# PiPowerHat.net
KiCad netlist of a schematic drawn in EAGLE
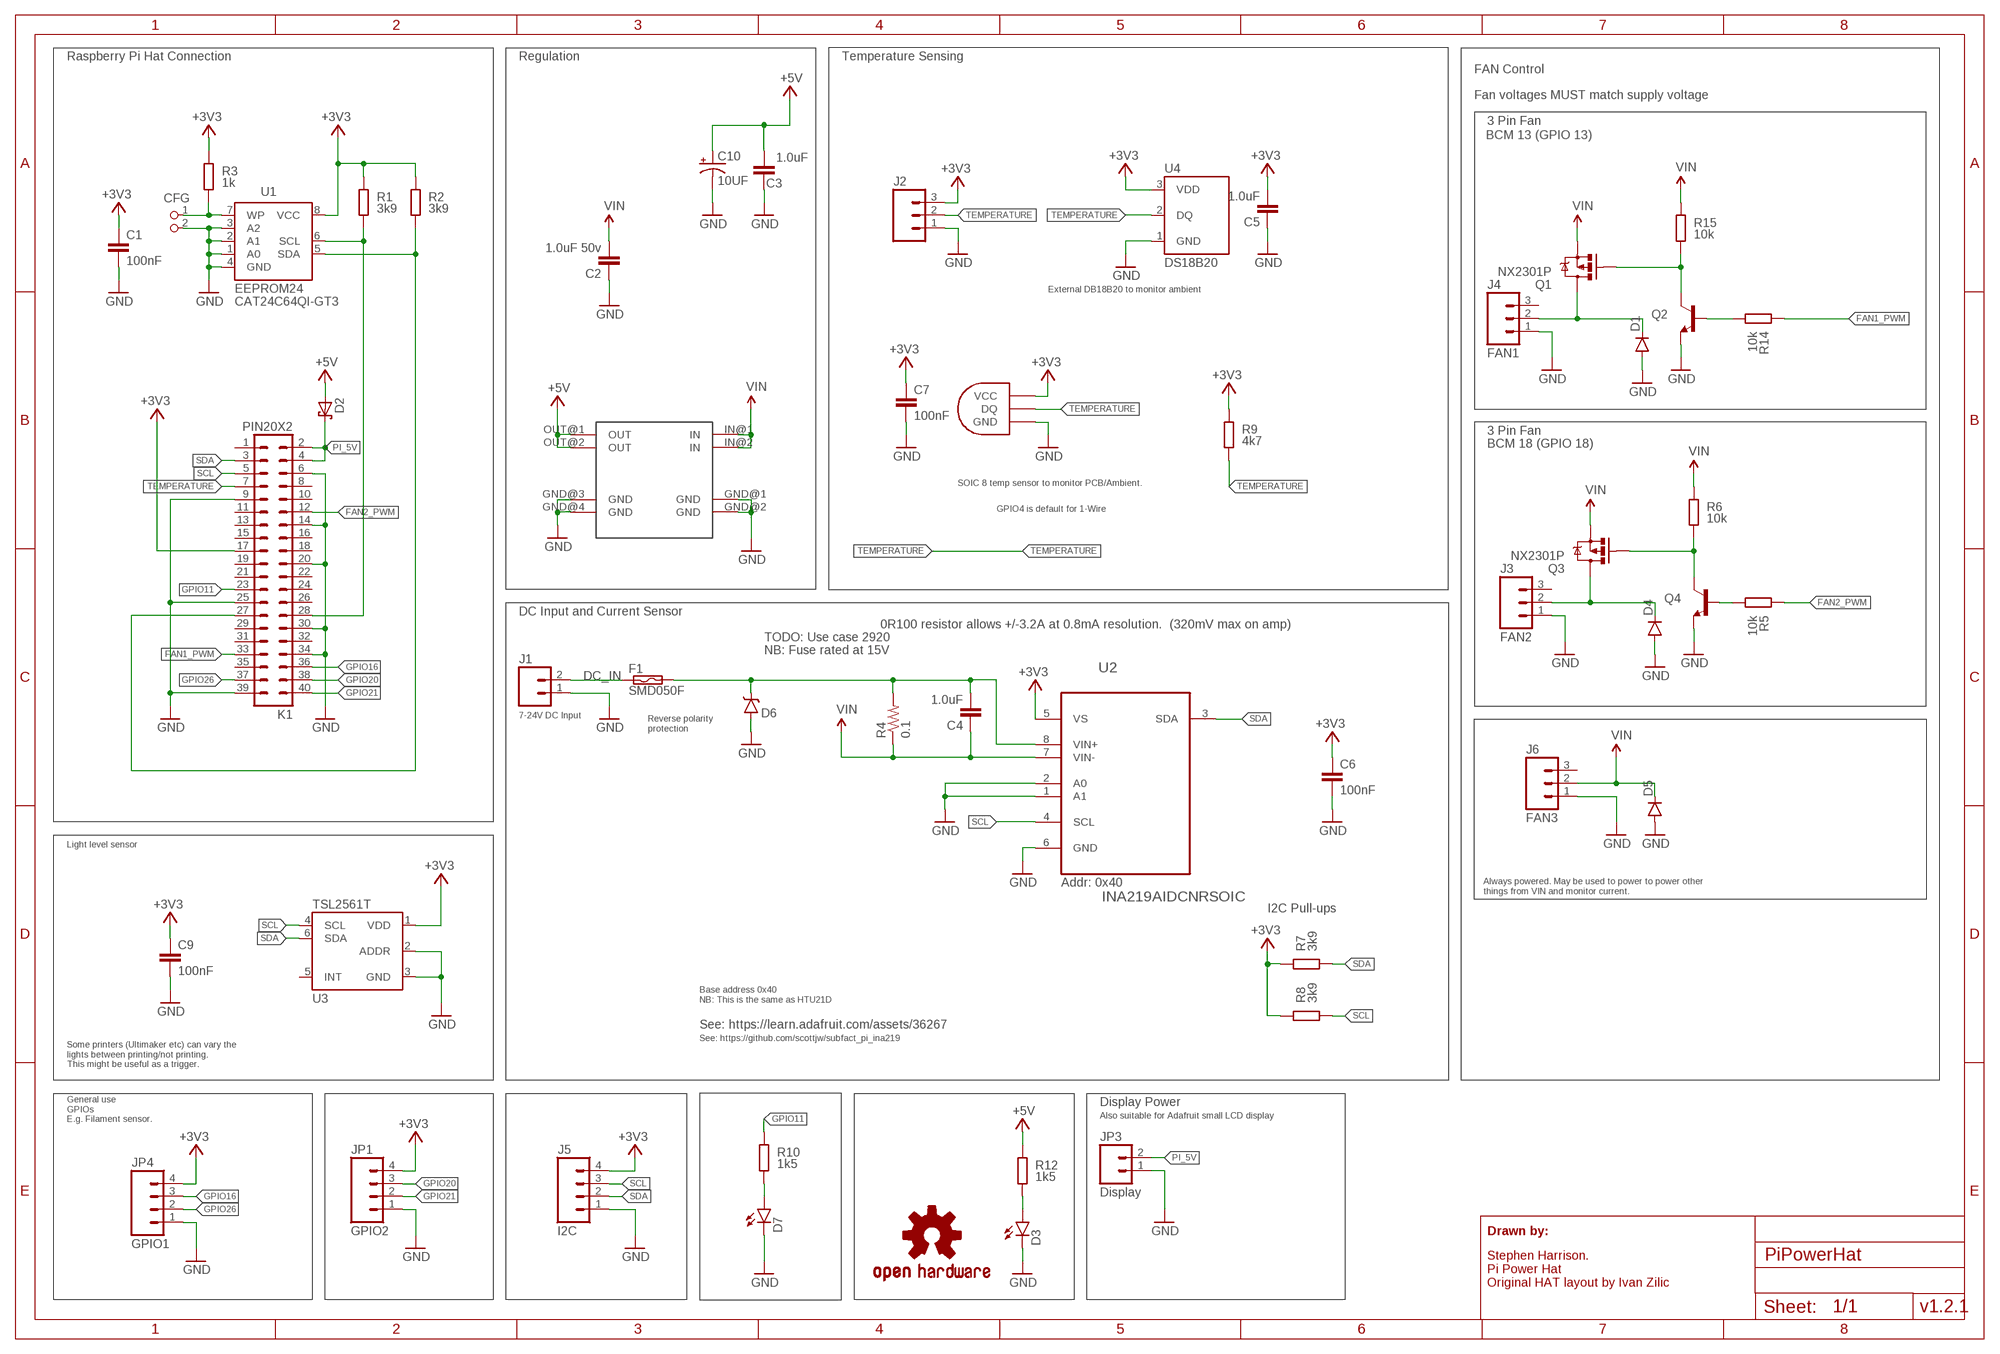
[diagram p0: schematic, sheet 1]

(export (version "E")
  (design (tool "Eeschema 10.0.6"))
  (components
    (comp (ref "C1")
      (value "100nF")
      (footprint "eagle-import:C0805K")
      (libsource (lib "eagle-import") (part "C-EUC0805K"))
    )
    (comp (ref "C2")
      (value "1.0uF 50v")
      (footprint "eagle-import:0805-CAP")
      (libsource (lib "eagle-import") (part "1.0UF-25V-+80/-20(0805){dblquote}"))
    )
    (comp (ref "C3")
      (value "1.0uF")
      (footprint "eagle-import:0805-CAP")
      (libsource (lib "eagle-import") (part "1.0UF-25V-+80/-20(0805){dblquote}"))
    )
    (comp (ref "C4")
      (value "1.0uF")
      (footprint "eagle-import:0805-CAP")
      (libsource (lib "eagle-import") (part "1.0UF-25V-+80/-20(0805){dblquote}"))
    )
    (comp (ref "C5")
      (value "1.0uF")
      (footprint "eagle-import:0805-CAP")
      (libsource (lib "eagle-import") (part "1.0UF-25V-+80/-20(0805){dblquote}"))
    )
    (comp (ref "C6")
      (value "100nF")
      (footprint "eagle-import:C0805K")
      (libsource (lib "eagle-import") (part "C-EUC0805K"))
    )
    (comp (ref "C7")
      (value "100nF")
      (footprint "eagle-import:C0805K")
      (libsource (lib "eagle-import") (part "C-EUC0805K"))
    )
    (comp (ref "C9")
      (value "100nF")
      (footprint "eagle-import:C0805K")
      (libsource (lib "eagle-import") (part "C-EUC0805K"))
    )
    (comp (ref "C10")
      (value "10UF")
      (footprint "eagle-import:EIA6032-NOM")
      (libsource (lib "eagle-import") (part "10UF-25V-10%(SMT-TANT)"))
    )
    (comp (ref "CFG")
      (value "PIN2_100")
      (footprint "eagle-import:PIN_W_2")
      (libsource (lib "eagle-import") (part "PIN2_100"))
    )
    (comp (ref "D1")
      (value "DIODESOD123")
      (footprint "eagle-import:SOD-123")
      (libsource (lib "eagle-import") (part "DIODESOD123"))
    )
    (comp (ref "D2")
      (value "MBRS340T3G")
      (footprint "eagle-import:SMC")
      (libsource (lib "eagle-import") (part "SCHOTTKY-DIODESMC"))
    )
    (comp (ref "D3")
      (value "LED1206-BOTTOM")
      (footprint "eagle-import:LED-1206-BOTTOM")
      (libsource (lib "eagle-import") (part "LED1206-BOTTOM"))
    )
    (comp (ref "D4")
      (value "DIODESOD123")
      (footprint "eagle-import:SOD-123")
      (libsource (lib "eagle-import") (part "DIODESOD123"))
    )
    (comp (ref "D5")
      (value "DIODESOD123")
      (footprint "eagle-import:SOD-123")
      (libsource (lib "eagle-import") (part "DIODESOD123"))
    )
    (comp (ref "D6")
      (value "B340A")
      (footprint "eagle-import:SMA-DIODE")
      (libsource (lib "eagle-import") (part "DIODE-SCHOTTKY-B340A"))
    )
    (comp (ref "D7")
      (value "LED1206")
      (footprint "eagle-import:LED-1206")
      (libsource (lib "eagle-import") (part "LED1206"))
    )
    (comp (ref "F1")
      (value "SMD050F")
      (footprint "eagle-import:SMD050F")
      (libsource (lib "eagle-import") (part "SMDF050"))
    )
    (comp (ref "J1")
      (value "M025MM")
      (footprint "eagle-import:SCREWTERMINAL-5MM-2")
      (libsource (lib "eagle-import") (part "M025MM"))
    )
    (comp (ref "J2")
      (value "M03POLAR")
      (footprint "eagle-import:MOLEX-1X3")
      (libsource (lib "eagle-import") (part "M03POLAR"))
    )
    (comp (ref "J3")
      (value "FAN2")
      (footprint "eagle-import:MOLEX-1X3")
      (libsource (lib "eagle-import") (part "M03POLAR"))
    )
    (comp (ref "J4")
      (value "FAN1")
      (footprint "eagle-import:MOLEX-1X3")
      (libsource (lib "eagle-import") (part "M03POLAR"))
    )
    (comp (ref "J5")
      (value "I2C")
      (footprint "eagle-import:MOLEX-1X4")
      (libsource (lib "eagle-import") (part "M04POLAR"))
    )
    (comp (ref "J6")
      (value "FAN3")
      (footprint "eagle-import:MOLEX-1X3")
      (libsource (lib "eagle-import") (part "M03POLAR"))
    )
    (comp (ref "JP1")
      (value "GPIO2")
      (footprint "eagle-import:MOLEX-1X4")
      (libsource (lib "eagle-import") (part "M04POLAR"))
    )
    (comp (ref "JP3")
      (value "Display")
      (footprint "eagle-import:MOLEX-1X2")
      (libsource (lib "eagle-import") (part "M02POLAR"))
    )
    (comp (ref "JP4")
      (value "GPIO1")
      (footprint "eagle-import:MOLEX-1X4")
      (libsource (lib "eagle-import") (part "M04POLAR"))
    )
    (comp (ref "K1")
      (value "PIN20X2")
      (footprint "eagle-import:PIN_20X2")
      (libsource (lib "eagle-import") (part "PIN20X2"))
    )
    (comp (ref "LOGO1")
      (value "OSHW-LOGOM")
      (footprint "eagle-import:OSHW-LOGO-M")
      (libsource (lib "eagle-import") (part "OSHW-LOGOM"))
    )
    (comp (ref "Q1")
      (value "NX2301P")
      (footprint "eagle-import:SOT23-3")
      (libsource (lib "eagle-import") (part "MOSFET-PCHANNEL"))
    )
    (comp (ref "Q2")
      (value "TRANSISTOR_NPNSOT23-3")
      (footprint "eagle-import:SOT23-3")
      (libsource (lib "eagle-import") (part "TRANSISTOR_NPNSOT23-3"))
    )
    (comp (ref "Q3")
      (value "NX2301P")
      (footprint "eagle-import:SOT23-3")
      (libsource (lib "eagle-import") (part "MOSFET-PCHANNEL"))
    )
    (comp (ref "Q4")
      (value "TRANSISTOR_NPNSOT23-3")
      (footprint "eagle-import:SOT23-3")
      (libsource (lib "eagle-import") (part "TRANSISTOR_NPNSOT23-3"))
    )
    (comp (ref "R1")
      (value "3k9")
      (footprint "eagle-import:M0805")
      (fields (field (name "TOLERANCE") "5%"))
      (libsource (lib "eagle-import") (part "R-EU_M0805"))
    )
    (comp (ref "R2")
      (value "3k9")
      (footprint "eagle-import:M0805")
      (fields (field (name "TOLERANCE") "5%"))
      (libsource (lib "eagle-import") (part "R-EU_M0805"))
    )
    (comp (ref "R3")
      (value "1k")
      (footprint "eagle-import:M0805")
      (fields (field (name "TOLERANCE") "5%"))
      (libsource (lib "eagle-import") (part "R-EU_M0805"))
    )
    (comp (ref "R4")
      (value "0.1")
      (footprint "eagle-import:2512")
      (libsource (lib "eagle-import") (part "0.001OHM-3W-1%(2512)3W/1%"))
    )
    (comp (ref "R5")
      (value "10k")
      (footprint "eagle-import:M0805")
      (fields (field (name "TOLERANCE") "5%"))
      (libsource (lib "eagle-import") (part "R-EU_M0805"))
    )
    (comp (ref "R6")
      (value "10k")
      (footprint "eagle-import:M0805")
      (fields (field (name "TOLERANCE") "5%"))
      (libsource (lib "eagle-import") (part "R-EU_M0805"))
    )
    (comp (ref "R7")
      (value "3k9")
      (footprint "eagle-import:M0805")
      (fields (field (name "TOLERANCE") "5%"))
      (libsource (lib "eagle-import") (part "R-EU_M0805"))
    )
    (comp (ref "R8")
      (value "3k9")
      (footprint "eagle-import:M0805")
      (fields (field (name "TOLERANCE") "5%"))
      (libsource (lib "eagle-import") (part "R-EU_M0805"))
    )
    (comp (ref "R9")
      (value "4k7")
      (footprint "eagle-import:M0805")
      (fields (field (name "TOLERANCE") "5%"))
      (libsource (lib "eagle-import") (part "R-EU_M0805"))
    )
    (comp (ref "R10")
      (value "1k5")
      (footprint "eagle-import:M0805")
      (fields (field (name "TOLERANCE") "5%"))
      (libsource (lib "eagle-import") (part "R-EU_M0805"))
    )
    (comp (ref "R12")
      (value "1k5")
      (footprint "eagle-import:M0805")
      (fields (field (name "TOLERANCE") "5%"))
      (libsource (lib "eagle-import") (part "R-EU_M0805"))
    )
    (comp (ref "R14")
      (value "10k")
      (footprint "eagle-import:M0805")
      (fields (field (name "TOLERANCE") "5%"))
      (libsource (lib "eagle-import") (part "R-EU_M0805"))
    )
    (comp (ref "R15")
      (value "10k")
      (footprint "eagle-import:M0805")
      (fields (field (name "TOLERANCE") "5%"))
      (libsource (lib "eagle-import") (part "R-EU_M0805"))
    )
    (comp (ref "RG1")
      (value "MINI-BUCK-MODULE-3A")
      (footprint "eagle-import:MINI-BUCK-MODULE-3A")
      (libsource (lib "eagle-import") (part "MINI-BUCK-MODULE-3A"))
    )
    (comp (ref "U1")
      (value "EEPROM24")
      (footprint "eagle-import:SOIC8")
      (libsource (lib "eagle-import") (part "EEPROM24"))
    )
    (comp (ref "U2")
      (value "INA219AIDCNRSOIC")
      (footprint "eagle-import:SO08")
      (libsource (lib "eagle-import") (part "INA219AIDCNRSOIC"))
    )
    (comp (ref "U3")
      (value "TSL2561T")
      (footprint "eagle-import:TMB-6")
      (libsource (lib "eagle-import") (part "TSL2561T"))
    )
    (comp (ref "U4")
      (value "DS18B20")
      (footprint "eagle-import:TO-92-AMMO")
      (libsource (lib "eagle-import") (part "DS18B20"))
    )
    (comp (ref "U5")
      (value "DS1820SOIC")
      (footprint "eagle-import:DS18B20_SOIC")
      (libsource (lib "eagle-import") (part "DS1820SOIC"))
    )
  )
  (nets
    (net (code "1") (name "+3V3") (class "Default")
      (node (ref "C1") (pin "1") (pinfunction "1_1") (pintype "passive"))
      (node (ref "C5") (pin "2") (pinfunction "2_2") (pintype "passive"))
      (node (ref "C6") (pin "1") (pinfunction "1_1") (pintype "passive"))
      (node (ref "C7") (pin "1") (pinfunction "1_1") (pintype "passive"))
      (node (ref "C9") (pin "1") (pinfunction "1_1") (pintype "passive"))
      (node (ref "J2") (pin "3") (pinfunction "3_3") (pintype "passive"))
      (node (ref "J5") (pin "4") (pinfunction "4_4") (pintype "passive"))
      (node (ref "JP1") (pin "4") (pinfunction "4_4") (pintype "passive"))
      (node (ref "JP4") (pin "4") (pinfunction "4_4") (pintype "passive"))
      (node (ref "K1") (pin "17") (pinfunction "17_17") (pintype "passive"))
      (node (ref "R1") (pin "2") (pinfunction "2_2") (pintype "passive"))
      (node (ref "R2") (pin "2") (pinfunction "2_2") (pintype "passive"))
      (node (ref "R3") (pin "2") (pinfunction "2_2") (pintype "passive"))
      (node (ref "R7") (pin "2") (pinfunction "2_2") (pintype "passive"))
      (node (ref "R8") (pin "2") (pinfunction "2_2") (pintype "passive"))
      (node (ref "R9") (pin "2") (pinfunction "2_2") (pintype "passive"))
      (node (ref "U1") (pin "8") (pinfunction "VCC_8") (pintype "power_in"))
      (node (ref "U2") (pin "5") (pinfunction "VS_5") (pintype "power_in"))
      (node (ref "U3") (pin "1") (pinfunction "VDD_1") (pintype "power_in"))
      (node (ref "U4") (pin "3") (pinfunction "VDD_3") (pintype "power_in"))
      (node (ref "U5") (pin "VCC") (pinfunction "VCC_VCC") (pintype "power_in"))
    )
    (net (code "2") (name "+5V") (class "Default")
      (node (ref "C10") (pin "A") (pinfunction "+_A") (pintype "passive"))
      (node (ref "C3") (pin "2") (pinfunction "2_2") (pintype "passive"))
      (node (ref "D2") (pin "A") (pinfunction "A_A") (pintype "passive"))
      (node (ref "R12") (pin "2") (pinfunction "2_2") (pintype "passive"))
      (node (ref "RG1") (pin "OUT@1") (pinfunction "OUT_OUT@1") (pintype "bidirectional"))
      (node (ref "RG1") (pin "OUT@2") (pinfunction "OUT_OUT@2") (pintype "bidirectional"))
    )
    (net (code "3") (name "/DC_IN") (class "Default")
      (node (ref "F1") (pin "1") (pinfunction "1_1") (pintype "passive"))
      (node (ref "J1") (pin "2") (pinfunction "2_2") (pintype "passive"))
    )
    (net (code "4") (name "FAN1_PWM") (class "Default")
      (node (ref "K1") (pin "33") (pinfunction "33_33") (pintype "passive"))
      (node (ref "R14") (pin "2") (pinfunction "2_2") (pintype "passive"))
    )
    (net (code "5") (name "FAN2_PWM") (class "Default")
      (node (ref "K1") (pin "12") (pinfunction "12_12") (pintype "passive"))
      (node (ref "R5") (pin "2") (pinfunction "2_2") (pintype "passive"))
    )
    (net (code "6") (name "GND") (class "Default")
      (node (ref "C1") (pin "2") (pinfunction "2_2") (pintype "passive"))
      (node (ref "C10") (pin "C") (pinfunction "-_C") (pintype "passive"))
      (node (ref "C2") (pin "1") (pinfunction "1_1") (pintype "passive"))
      (node (ref "C3") (pin "1") (pinfunction "1_1") (pintype "passive"))
      (node (ref "C5") (pin "1") (pinfunction "1_1") (pintype "passive"))
      (node (ref "C6") (pin "2") (pinfunction "2_2") (pintype "passive"))
      (node (ref "C7") (pin "2") (pinfunction "2_2") (pintype "passive"))
      (node (ref "C9") (pin "2") (pinfunction "2_2") (pintype "passive"))
      (node (ref "CFG") (pin "2") (pinfunction "2_2") (pintype "passive"))
      (node (ref "D1") (pin "A") (pinfunction "A_A") (pintype "passive"))
      (node (ref "D3") (pin "C") (pinfunction "C_C") (pintype "passive"))
      (node (ref "D4") (pin "A") (pinfunction "A_A") (pintype "passive"))
      (node (ref "D5") (pin "A") (pinfunction "A_A") (pintype "passive"))
      (node (ref "D6") (pin "A") (pinfunction "A_A") (pintype "passive"))
      (node (ref "D7") (pin "C") (pinfunction "C_C") (pintype "passive"))
      (node (ref "J1") (pin "1") (pinfunction "1_1") (pintype "passive"))
      (node (ref "J2") (pin "1") (pinfunction "1_1") (pintype "passive"))
      (node (ref "J3") (pin "1") (pinfunction "1_1") (pintype "passive"))
      (node (ref "J4") (pin "1") (pinfunction "1_1") (pintype "passive"))
      (node (ref "J5") (pin "1") (pinfunction "1_1") (pintype "passive"))
      (node (ref "J6") (pin "1") (pinfunction "1_1") (pintype "passive"))
      (node (ref "JP1") (pin "1") (pinfunction "1_1") (pintype "passive"))
      (node (ref "JP3") (pin "1") (pinfunction "1_1") (pintype "passive"))
      (node (ref "JP4") (pin "1") (pinfunction "1_1") (pintype "passive"))
      (node (ref "K1") (pin "14") (pinfunction "14_14") (pintype "passive"))
      (node (ref "K1") (pin "20") (pinfunction "20_20") (pintype "passive"))
      (node (ref "K1") (pin "25") (pinfunction "25_25") (pintype "passive"))
      (node (ref "K1") (pin "30") (pinfunction "30_30") (pintype "passive"))
      (node (ref "K1") (pin "34") (pinfunction "34_34") (pintype "passive"))
      (node (ref "K1") (pin "39") (pinfunction "39_39") (pintype "passive"))
      (node (ref "K1") (pin "6") (pinfunction "6_6") (pintype "passive"))
      (node (ref "K1") (pin "9") (pinfunction "9_9") (pintype "passive"))
      (node (ref "Q2") (pin "2") (pinfunction "E_2") (pintype "passive"))
      (node (ref "Q4") (pin "2") (pinfunction "E_2") (pintype "passive"))
      (node (ref "RG1") (pin "GND@1") (pinfunction "GND_GND@1") (pintype "bidirectional"))
      (node (ref "RG1") (pin "GND@2") (pinfunction "GND_GND@2") (pintype "bidirectional"))
      (node (ref "RG1") (pin "GND@3") (pinfunction "GND_GND@3") (pintype "bidirectional"))
      (node (ref "RG1") (pin "GND@4") (pinfunction "GND_GND@4") (pintype "bidirectional"))
      (node (ref "U1") (pin "1") (pinfunction "A0_1") (pintype "input"))
      (node (ref "U1") (pin "2") (pinfunction "A1_2") (pintype "input"))
      (node (ref "U1") (pin "3") (pinfunction "A2_3") (pintype "input"))
      (node (ref "U1") (pin "4") (pinfunction "GND_4") (pintype "power_in"))
      (node (ref "U2") (pin "1") (pinfunction "A1_1") (pintype "input"))
      (node (ref "U2") (pin "2") (pinfunction "A0_2") (pintype "input"))
      (node (ref "U2") (pin "6") (pinfunction "GND_6") (pintype "passive"))
      (node (ref "U3") (pin "2") (pinfunction "ADDR_2") (pintype "input"))
      (node (ref "U3") (pin "3") (pinfunction "GND_3") (pintype "power_in"))
      (node (ref "U4") (pin "1") (pinfunction "GND_1") (pintype "power_in"))
      (node (ref "U5") (pin "GND") (pinfunction "GND_GND") (pintype "power_in"))
    )
    (net (code "7") (name "GPIO11") (class "Default")
      (node (ref "K1") (pin "23") (pinfunction "23_23") (pintype "passive"))
      (node (ref "R10") (pin "2") (pinfunction "2_2") (pintype "passive"))
    )
    (net (code "8") (name "GPIO16") (class "Default")
      (node (ref "JP4") (pin "3") (pinfunction "3_3") (pintype "passive"))
      (node (ref "K1") (pin "36") (pinfunction "36_36") (pintype "passive"))
    )
    (net (code "9") (name "GPIO20") (class "Default")
      (node (ref "JP1") (pin "3") (pinfunction "3_3") (pintype "passive"))
      (node (ref "K1") (pin "38") (pinfunction "38_38") (pintype "passive"))
    )
    (net (code "10") (name "GPIO21") (class "Default")
      (node (ref "JP1") (pin "2") (pinfunction "2_2") (pintype "passive"))
      (node (ref "K1") (pin "40") (pinfunction "40_40") (pintype "passive"))
    )
    (net (code "11") (name "GPIO26") (class "Default")
      (node (ref "JP4") (pin "2") (pinfunction "2_2") (pintype "passive"))
      (node (ref "K1") (pin "37") (pinfunction "37_37") (pintype "passive"))
    )
    (net (code "12") (name "Net-(D3-PadA)") (class "Default")
      (node (ref "D3") (pin "A") (pinfunction "A_A") (pintype "passive"))
      (node (ref "R12") (pin "1") (pinfunction "1_1") (pintype "passive"))
    )
    (net (code "13") (name "Net-(D7-PadA)") (class "Default")
      (node (ref "D7") (pin "A") (pinfunction "A_A") (pintype "passive"))
      (node (ref "R10") (pin "1") (pinfunction "1_1") (pintype "passive"))
    )
    (net (code "14") (name "Net-(Q1-D)") (class "Default")
      (node (ref "D1") (pin "C") (pinfunction "C_C") (pintype "passive"))
      (node (ref "J4") (pin "2") (pinfunction "2_2") (pintype "passive"))
      (node (ref "Q1") (pin "3") (pinfunction "D_3") (pintype "passive"))
    )
    (net (code "15") (name "Net-(Q1-G)") (class "Default")
      (node (ref "Q1") (pin "1") (pinfunction "G_1") (pintype "passive"))
      (node (ref "Q2") (pin "3") (pinfunction "C_3") (pintype "passive"))
      (node (ref "R15") (pin "1") (pinfunction "1_1") (pintype "passive"))
    )
    (net (code "16") (name "Net-(Q2-B)") (class "Default")
      (node (ref "Q2") (pin "1") (pinfunction "B_1") (pintype "passive"))
      (node (ref "R14") (pin "1") (pinfunction "1_1") (pintype "passive"))
    )
    (net (code "17") (name "Net-(Q3-D)") (class "Default")
      (node (ref "D4") (pin "C") (pinfunction "C_C") (pintype "passive"))
      (node (ref "J3") (pin "2") (pinfunction "2_2") (pintype "passive"))
      (node (ref "Q3") (pin "3") (pinfunction "D_3") (pintype "passive"))
    )
    (net (code "18") (name "Net-(Q3-G)") (class "Default")
      (node (ref "Q3") (pin "1") (pinfunction "G_1") (pintype "passive"))
      (node (ref "Q4") (pin "3") (pinfunction "C_3") (pintype "passive"))
      (node (ref "R6") (pin "1") (pinfunction "1_1") (pintype "passive"))
    )
    (net (code "19") (name "Net-(Q4-B)") (class "Default")
      (node (ref "Q4") (pin "1") (pinfunction "B_1") (pintype "passive"))
      (node (ref "R5") (pin "1") (pinfunction "1_1") (pintype "passive"))
    )
    (net (code "20") (name "Net-(U1-SCL)") (class "Default")
      (node (ref "K1") (pin "28") (pinfunction "28_28") (pintype "passive"))
      (node (ref "R1") (pin "1") (pinfunction "1_1") (pintype "passive"))
      (node (ref "U1") (pin "6") (pinfunction "SCL_6") (pintype "input"))
    )
    (net (code "21") (name "Net-(U1-SDA)") (class "Default")
      (node (ref "K1") (pin "27") (pinfunction "27_27") (pintype "passive"))
      (node (ref "R2") (pin "1") (pinfunction "1_1") (pintype "passive"))
      (node (ref "U1") (pin "5") (pinfunction "SDA_5") (pintype "bidirectional"))
    )
    (net (code "22") (name "Net-(U1-WP)") (class "Default")
      (node (ref "CFG") (pin "1") (pinfunction "1_1") (pintype "passive"))
      (node (ref "R3") (pin "1") (pinfunction "1_1") (pintype "passive"))
      (node (ref "U1") (pin "7") (pinfunction "WP_7") (pintype "input"))
    )
    (net (code "23") (name "Net-(U2-VIN+)") (class "Default")
      (node (ref "C4") (pin "2") (pinfunction "2_2") (pintype "passive"))
      (node (ref "D6") (pin "C") (pinfunction "C_C") (pintype "passive"))
      (node (ref "F1") (pin "2") (pinfunction "2_2") (pintype "passive"))
      (node (ref "R4") (pin "2") (pinfunction "2_2") (pintype "passive"))
      (node (ref "U2") (pin "8") (pinfunction "VIN+_8") (pintype "input"))
    )
    (net (code "24") (name "PI_5V") (class "Default")
      (node (ref "D2") (pin "C") (pinfunction "C_C") (pintype "passive"))
      (node (ref "JP3") (pin "2") (pinfunction "2_2") (pintype "passive"))
      (node (ref "K1") (pin "2") (pinfunction "2_2") (pintype "passive"))
      (node (ref "K1") (pin "4") (pinfunction "4_4") (pintype "passive"))
    )
    (net (code "25") (name "SCL") (class "Default")
      (node (ref "J5") (pin "3") (pinfunction "3_3") (pintype "passive"))
      (node (ref "K1") (pin "5") (pinfunction "5_5") (pintype "passive"))
      (node (ref "R8") (pin "1") (pinfunction "1_1") (pintype "passive"))
      (node (ref "U2") (pin "4") (pinfunction "SCL_4") (pintype "input"))
      (node (ref "U3") (pin "4") (pinfunction "SCL_4") (pintype "input"))
    )
    (net (code "26") (name "SDA") (class "Default")
      (node (ref "J5") (pin "2") (pinfunction "2_2") (pintype "passive"))
      (node (ref "K1") (pin "3") (pinfunction "3_3") (pintype "passive"))
      (node (ref "R7") (pin "1") (pinfunction "1_1") (pintype "passive"))
      (node (ref "U2") (pin "3") (pinfunction "SDA_3") (pintype "bidirectional"))
      (node (ref "U3") (pin "6") (pinfunction "SDA_6") (pintype "bidirectional"))
    )
    (net (code "27") (name "TEMPERATURE") (class "Default")
      (node (ref "J2") (pin "2") (pinfunction "2_2") (pintype "passive"))
      (node (ref "K1") (pin "7") (pinfunction "7_7") (pintype "passive"))
      (node (ref "R9") (pin "1") (pinfunction "1_1") (pintype "passive"))
      (node (ref "U4") (pin "2") (pinfunction "DQ_2") (pintype "bidirectional"))
      (node (ref "U5") (pin "DQ") (pinfunction "DQ_DQ") (pintype "bidirectional"))
    )
    (net (code "28") (name "VIN") (class "Default")
      (node (ref "C2") (pin "2") (pinfunction "2_2") (pintype "passive"))
      (node (ref "C4") (pin "1") (pinfunction "1_1") (pintype "passive"))
      (node (ref "D5") (pin "C") (pinfunction "C_C") (pintype "passive"))
      (node (ref "J6") (pin "2") (pinfunction "2_2") (pintype "passive"))
      (node (ref "Q1") (pin "2") (pinfunction "S_2") (pintype "passive"))
      (node (ref "Q3") (pin "2") (pinfunction "S_2") (pintype "passive"))
      (node (ref "R15") (pin "2") (pinfunction "2_2") (pintype "passive"))
      (node (ref "R4") (pin "1") (pinfunction "1_1") (pintype "passive"))
      (node (ref "R6") (pin "2") (pinfunction "2_2") (pintype "passive"))
      (node (ref "RG1") (pin "IN@1") (pinfunction "IN_IN@1") (pintype "bidirectional"))
      (node (ref "RG1") (pin "IN@2") (pinfunction "IN_IN@2") (pintype "bidirectional"))
      (node (ref "U2") (pin "7") (pinfunction "VIN-_7") (pintype "input"))
    )
    (net (code "29") (name "unconnected-(J3-Pad3)") (class "Default")
      (node (ref "J3") (pin "3") (pinfunction "3_3") (pintype "passive"))
    )
    (net (code "30") (name "unconnected-(J4-Pad3)") (class "Default")
      (node (ref "J4") (pin "3") (pinfunction "3_3") (pintype "passive"))
    )
    (net (code "31") (name "unconnected-(J6-Pad3)") (class "Default")
      (node (ref "J6") (pin "3") (pinfunction "3_3") (pintype "passive"))
    )
    (net (code "32") (name "unconnected-(K1-Pad1)") (class "Default")
      (node (ref "K1") (pin "1") (pinfunction "1_1") (pintype "passive"))
    )
    (net (code "33") (name "unconnected-(K1-Pad8)") (class "Default")
      (node (ref "K1") (pin "8") (pinfunction "8_8") (pintype "passive"))
    )
    (net (code "34") (name "unconnected-(K1-Pad10)") (class "Default")
      (node (ref "K1") (pin "10") (pinfunction "10_10") (pintype "passive"))
    )
    (net (code "35") (name "unconnected-(K1-Pad11)") (class "Default")
      (node (ref "K1") (pin "11") (pinfunction "11_11") (pintype "passive"))
    )
    (net (code "36") (name "unconnected-(K1-Pad13)") (class "Default")
      (node (ref "K1") (pin "13") (pinfunction "13_13") (pintype "passive"))
    )
    (net (code "37") (name "unconnected-(K1-Pad15)") (class "Default")
      (node (ref "K1") (pin "15") (pinfunction "15_15") (pintype "passive"))
    )
    (net (code "38") (name "unconnected-(K1-Pad16)") (class "Default")
      (node (ref "K1") (pin "16") (pinfunction "16_16") (pintype "passive"))
    )
    (net (code "39") (name "unconnected-(K1-Pad18)") (class "Default")
      (node (ref "K1") (pin "18") (pinfunction "18_18") (pintype "passive"))
    )
    (net (code "40") (name "unconnected-(K1-Pad19)") (class "Default")
      (node (ref "K1") (pin "19") (pinfunction "19_19") (pintype "passive"))
    )
    (net (code "41") (name "unconnected-(K1-Pad21)") (class "Default")
      (node (ref "K1") (pin "21") (pinfunction "21_21") (pintype "passive"))
    )
    (net (code "42") (name "unconnected-(K1-Pad22)") (class "Default")
      (node (ref "K1") (pin "22") (pinfunction "22_22") (pintype "passive"))
    )
    (net (code "43") (name "unconnected-(K1-Pad24)") (class "Default")
      (node (ref "K1") (pin "24") (pinfunction "24_24") (pintype "passive"))
    )
    (net (code "44") (name "unconnected-(K1-Pad26)") (class "Default")
      (node (ref "K1") (pin "26") (pinfunction "26_26") (pintype "passive"))
    )
    (net (code "45") (name "unconnected-(K1-Pad29)") (class "Default")
      (node (ref "K1") (pin "29") (pinfunction "29_29") (pintype "passive"))
    )
    (net (code "46") (name "unconnected-(K1-Pad31)") (class "Default")
      (node (ref "K1") (pin "31") (pinfunction "31_31") (pintype "passive"))
    )
    (net (code "47") (name "unconnected-(K1-Pad32)") (class "Default")
      (node (ref "K1") (pin "32") (pinfunction "32_32") (pintype "passive"))
    )
    (net (code "48") (name "unconnected-(K1-Pad35)") (class "Default")
      (node (ref "K1") (pin "35") (pinfunction "35_35") (pintype "passive"))
    )
    (net (code "49") (name "unconnected-(U3-INT-Pad5)") (class "Default")
      (node (ref "U3") (pin "5") (pinfunction "INT_5") (pintype "output"))
    )
  )
)
